# 4Show.net
KiCad netlist of a schematic drawn in EAGLE
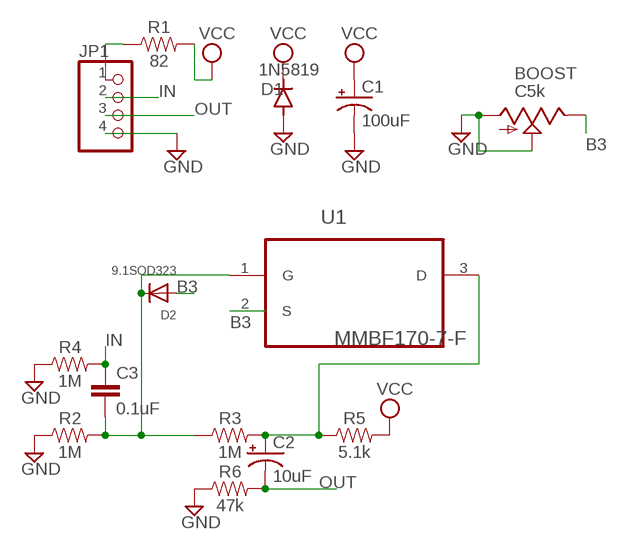
[diagram p0: schematic, sheet 1]

(export (version "E")
  (design (tool "Eeschema 10.0.6"))
  (components
    (comp (ref "BOOST")
      (value "C5k")
      (footprint "eagle-import:9MM_SNAP-IN_POT")
      (libsource (lib "eagle-import") (part "9MM_SNAP-IN_POT_"))
    )
    (comp (ref "C1")
      (value "100uF")
      (footprint "eagle-import:PAN_B_SMD+THRU")
      (libsource (lib "eagle-import") (part "CAP_SMD+THRUPAN_B"))
    )
    (comp (ref "C2")
      (value "10uF")
      (footprint "eagle-import:PAN_B_SMD+THRU")
      (libsource (lib "eagle-import") (part "CAP_SMD+THRUPAN_B"))
    )
    (comp (ref "C3")
      (value "0.1uF")
      (footprint "eagle-import:0603")
      (libsource (lib "eagle-import") (part "0.1UF-0603-25V-(+80/-20%)"))
    )
    (comp (ref "D1")
      (value "1N5819")
      (footprint "eagle-import:SOD123")
      (libsource (lib "eagle-import") (part "DIODE-SOD123"))
    )
    (comp (ref "D2")
      (value "9.1SOD323")
      (footprint "eagle-import:SOD-323F")
      (libsource (lib "eagle-import") (part "DIODESOD-323F"))
    )
    (comp (ref "JP1")
      (value "PINHD-1X4")
      (footprint "eagle-import:1X04")
      (libsource (lib "eagle-import") (part "PINHD-1X4"))
    )
    (comp (ref "R1")
      (value "82")
      (footprint "eagle-import:0603")
      (libsource (lib "eagle-import") (part "82OHM-0603-1/10W-1%"))
    )
    (comp (ref "R2")
      (value "1M")
      (footprint "eagle-import:0603")
      (libsource (lib "eagle-import") (part "1MOHM-0603-1/4W-5%"))
    )
    (comp (ref "R3")
      (value "1M")
      (footprint "eagle-import:0603")
      (libsource (lib "eagle-import") (part "1MOHM-0603-1/4W-5%"))
    )
    (comp (ref "R4")
      (value "1M")
      (footprint "eagle-import:0603")
      (libsource (lib "eagle-import") (part "1MOHM-0603-1/4W-5%"))
    )
    (comp (ref "R5")
      (value "5.1k")
      (footprint "eagle-import:0603")
      (libsource (lib "eagle-import") (part "5.6KOHM-0603-1/10W-1%"))
    )
    (comp (ref "R6")
      (value "47k")
      (footprint "eagle-import:0603")
      (libsource (lib "eagle-import") (part "47KOHM-0603-1/10W-1%"))
    )
    (comp (ref "U1")
      (value "MMBF170-7-F")
      (footprint "eagle-import:SOT103P240X110-3N")
      (fields (field (name "MF") "Diodes Inc."))
      (libsource (lib "eagle-import") (part "MMBF170-7-F"))
    )
  )
  (nets
    (net (code "1") (name "/B3") (class "Default")
      (node (ref "BOOST") (pin "3") (pinfunction "E_3") (pintype "passive"))
      (node (ref "D2") (pin "A") (pinfunction "A_A") (pintype "passive"))
      (node (ref "U1") (pin "2") (pinfunction "S_2") (pintype "passive"))
    )
    (net (code "2") (name "/IN") (class "Default")
      (node (ref "C3") (pin "1") (pinfunction "1_1") (pintype "passive"))
      (node (ref "JP1") (pin "2") (pinfunction "2_2") (pintype "passive"))
      (node (ref "R4") (pin "2") (pinfunction "2_2") (pintype "passive"))
    )
    (net (code "3") (name "/OUT") (class "Default")
      (node (ref "C2") (pin "-") (pinfunction "-_-") (pintype "passive"))
      (node (ref "C2") (pin "--") (pinfunction "-_--") (pintype "passive"))
      (node (ref "JP1") (pin "3") (pinfunction "3_3") (pintype "passive"))
      (node (ref "R6") (pin "2") (pinfunction "2_2") (pintype "passive"))
    )
    (net (code "4") (name "GND") (class "Default")
      (node (ref "BOOST") (pin "1") (pinfunction "A_1") (pintype "passive"))
      (node (ref "BOOST") (pin "2") (pinfunction "S_2") (pintype "passive"))
      (node (ref "C1") (pin "-") (pinfunction "-_-") (pintype "passive"))
      (node (ref "C1") (pin "--") (pinfunction "-_--") (pintype "passive"))
      (node (ref "D1") (pin "A") (pinfunction "A_A") (pintype "passive"))
      (node (ref "JP1") (pin "4") (pinfunction "4_4") (pintype "passive"))
      (node (ref "R2") (pin "1") (pinfunction "1_1") (pintype "passive"))
      (node (ref "R4") (pin "1") (pinfunction "1_1") (pintype "passive"))
      (node (ref "R6") (pin "1") (pinfunction "1_1") (pintype "passive"))
    )
    (net (code "5") (name "Net-(JP1-Pad1)") (class "Default")
      (node (ref "JP1") (pin "1") (pinfunction "1_1") (pintype "passive"))
      (node (ref "R1") (pin "1") (pinfunction "1_1") (pintype "passive"))
    )
    (net (code "6") (name "Net-(U1-D)") (class "Default")
      (node (ref "C2") (pin "+") (pinfunction "+_+") (pintype "passive"))
      (node (ref "C2") (pin "++") (pinfunction "+_++") (pintype "passive"))
      (node (ref "R3") (pin "2") (pinfunction "2_2") (pintype "passive"))
      (node (ref "R5") (pin "1") (pinfunction "1_1") (pintype "passive"))
      (node (ref "U1") (pin "3") (pinfunction "D_3") (pintype "output"))
    )
    (net (code "7") (name "Net-(U1-G)") (class "Default")
      (node (ref "C3") (pin "2") (pinfunction "2_2") (pintype "passive"))
      (node (ref "D2") (pin "C") (pinfunction "C_C") (pintype "passive"))
      (node (ref "R2") (pin "2") (pinfunction "2_2") (pintype "passive"))
      (node (ref "R3") (pin "1") (pinfunction "1_1") (pintype "passive"))
      (node (ref "U1") (pin "1") (pinfunction "G_1") (pintype "input"))
    )
    (net (code "8") (name "VCC") (class "Default")
      (node (ref "C1") (pin "+") (pinfunction "+_+") (pintype "passive"))
      (node (ref "C1") (pin "++") (pinfunction "+_++") (pintype "passive"))
      (node (ref "D1") (pin "C") (pinfunction "C_C") (pintype "passive"))
      (node (ref "R1") (pin "2") (pinfunction "2_2") (pintype "passive"))
      (node (ref "R5") (pin "2") (pinfunction "2_2") (pintype "passive"))
    )
  )
)
